# Power.net
KiCad netlist of a schematic drawn in Altium Designer
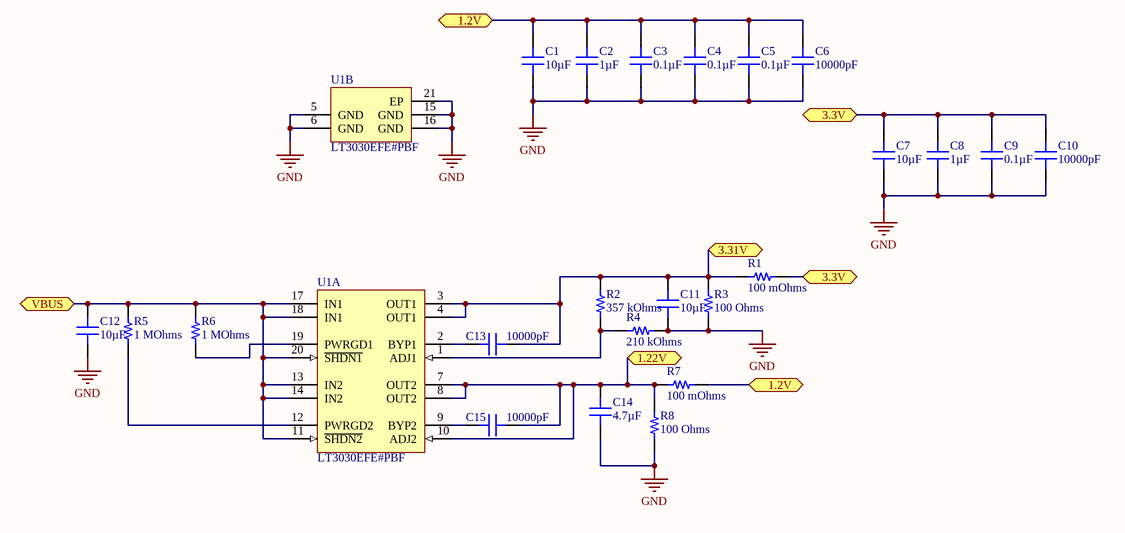
[diagram p0: Power.SchDoc]

(export (version "E")
  (design (tool "Eeschema 10.0.6"))
  (components
    (comp (ref "C1")
      (value "10µF")
      (footprint "CAP 0805_2012")
      (description "CAP CER 10UF 16V X5R 0805")
      (fields
        (field (name "PART NUMBER") "CL21A106KOQNNNG")
        (field (name "MANUFACTURER") "Samsung Electro-Mechanics")
      )
      (libsource (lib "Celestial Altium Library - altium_library") (part "Capacitor"))
    )
    (comp (ref "C2")
      (value "1µF")
      (footprint "CAP 0805_2012")
      (description "CAP CER 1UF 25V X7R 0805")
      (fields
        (field (name "PART NUMBER") "CL21B105KAFNNNE")
        (field (name "MANUFACTURER") "Samsung Electro-Mechanics")
      )
      (libsource (lib "Celestial Altium Library - altium_library") (part "Capacitor"))
    )
    (comp (ref "C3")
      (value "0.1µF")
      (footprint "CAP 0805_2012")
      (description "CAP CER 0.1UF 50V X7R 0805")
      (fields
        (field (name "PART NUMBER") "CL21B104KBCNNNC")
        (field (name "MANUFACTURER") "Samsung Electro-Mechanics")
      )
      (libsource (lib "Celestial Altium Library - altium_library") (part "Capacitor"))
    )
    (comp (ref "C4")
      (value "0.1µF")
      (footprint "CAP 0805_2012")
      (description "CAP CER 0.1UF 50V X7R 0805")
      (fields
        (field (name "PART NUMBER") "CL21B104KBCNNNC")
        (field (name "MANUFACTURER") "Samsung Electro-Mechanics")
      )
      (libsource (lib "Celestial Altium Library - altium_library") (part "Capacitor"))
    )
    (comp (ref "C5")
      (value "0.1µF")
      (footprint "CAP 0805_2012")
      (description "CAP CER 0.1UF 50V X7R 0805")
      (fields
        (field (name "PART NUMBER") "CL21B104KBCNNNC")
        (field (name "MANUFACTURER") "Samsung Electro-Mechanics")
      )
      (libsource (lib "Celestial Altium Library - altium_library") (part "Capacitor"))
    )
    (comp (ref "C6")
      (value "10000pF")
      (footprint "CAP 0805_2012")
      (description "CAP CER 10000PF 50V X7R 0805")
      (fields
        (field (name "PART NUMBER") "CL21B103KBANNNC")
        (field (name "MANUFACTURER") "Samsung Electro-Mechanics")
      )
      (libsource (lib "Celestial Altium Library - altium_library") (part "Capacitor"))
    )
    (comp (ref "C7")
      (value "10µF")
      (footprint "CAP 0805_2012")
      (description "CAP CER 10UF 16V X5R 0805")
      (fields
        (field (name "PART NUMBER") "CL21A106KOQNNNG")
        (field (name "MANUFACTURER") "Samsung Electro-Mechanics")
      )
      (libsource (lib "Celestial Altium Library - altium_library") (part "Capacitor"))
    )
    (comp (ref "C8")
      (value "1µF")
      (footprint "CAP 0805_2012")
      (description "CAP CER 1UF 25V X7R 0805")
      (fields
        (field (name "PART NUMBER") "CL21B105KAFNNNE")
        (field (name "MANUFACTURER") "Samsung Electro-Mechanics")
      )
      (libsource (lib "Celestial Altium Library - altium_library") (part "Capacitor"))
    )
    (comp (ref "C9")
      (value "0.1µF")
      (footprint "CAP 0805_2012")
      (description "CAP CER 0.1UF 50V X7R 0805")
      (fields
        (field (name "PART NUMBER") "CL21B104KBCNNNC")
        (field (name "MANUFACTURER") "Samsung Electro-Mechanics")
      )
      (libsource (lib "Celestial Altium Library - altium_library") (part "Capacitor"))
    )
    (comp (ref "C10")
      (value "10000pF")
      (footprint "CAP 0805_2012")
      (description "CAP CER 10000PF 50V X7R 0805")
      (fields
        (field (name "PART NUMBER") "CL21B103KBANNNC")
        (field (name "MANUFACTURER") "Samsung Electro-Mechanics")
      )
      (libsource (lib "Celestial Altium Library - altium_library") (part "Capacitor"))
    )
    (comp (ref "C11")
      (value "10µF")
      (footprint "CAP 0805_2012")
      (description "CAP CER 10UF 16V X5R 0805")
      (fields
        (field (name "PART NUMBER") "CL21A106KOQNNNG")
        (field (name "MANUFACTURER") "Samsung Electro-Mechanics")
      )
      (libsource (lib "Celestial Altium Library - altium_library") (part "Capacitor"))
    )
    (comp (ref "C12")
      (value "10µF")
      (footprint "CAP 0805_2012")
      (description "CAP CER 10UF 16V X5R 0805")
      (fields
        (field (name "PART NUMBER") "CL21A106KOQNNNG")
        (field (name "MANUFACTURER") "Samsung Electro-Mechanics")
      )
      (libsource (lib "Celestial Altium Library - altium_library") (part "Capacitor"))
    )
    (comp (ref "C13")
      (value "10000pF")
      (footprint "CAP 0805_2012")
      (description "CAP CER 10000PF 50V X7R 0805")
      (fields
        (field (name "PART NUMBER") "CL21B103KBANNNC")
        (field (name "MANUFACTURER") "Samsung Electro-Mechanics")
      )
      (libsource (lib "Celestial Altium Library - altium_library") (part "Capacitor"))
    )
    (comp (ref "C14")
      (value "4.7µF")
      (footprint "CAP 0805_2012")
      (description "CAP CER 4.7UF 25V X5R 0805")
      (fields
        (field (name "PART NUMBER") "CL21A475KAQNNNE")
        (field (name "MANUFACTURER") "Samsung Electro-Mechanics")
      )
      (libsource (lib "Celestial Altium Library - altium_library") (part "Capacitor"))
    )
    (comp (ref "C15")
      (value "10000pF")
      (footprint "CAP 0805_2012")
      (description "CAP CER 10000PF 50V X7R 0805")
      (fields
        (field (name "PART NUMBER") "CL21B103KBANNNC")
        (field (name "MANUFACTURER") "Samsung Electro-Mechanics")
      )
      (libsource (lib "Celestial Altium Library - altium_library") (part "Capacitor"))
    )
    (comp (ref "R1")
      (value "100 mOhms")
      (footprint "RES 0805_2012")
      (description "RES 0.1 OHM 1% 1/3W 0805")
      (fields (field (name "PART NUMBER") "RL1220S-R10-F") (field (name "MANUFACTURER") "Susumu"))
      (libsource (lib "Celestial Altium Library - altium_library") (part "Resistor"))
    )
    (comp (ref "R2")
      (value "357 kOhms")
      (footprint "RES 0805_2012")
      (description "RES SMD 357K OHM 1% 1/8W 0805")
      (fields
        (field (name "PART NUMBER") "ERJ-6ENF3573V")
        (field (name "MANUFACTURER") "Panasonic Electronic Components")
      )
      (libsource (lib "Celestial Altium Library - altium_library") (part "Resistor"))
    )
    (comp (ref "R3")
      (value "100 Ohms")
      (footprint "RES 0805_2012")
      (description "RES 100 OHM 1% 1/4W 0805")
      (fields
        (field (name "PART NUMBER") "RNCP0805FTD100R")
        (field (name "MANUFACTURER") "Stackpole Electronics Inc")
      )
      (libsource (lib "Celestial Altium Library - altium_library") (part "Resistor"))
    )
    (comp (ref "R4")
      (value "210 kOhms")
      (footprint "RES 0805_2012")
      (description "RES SMD 210K OHM 1% 1/8W 0805")
      (fields
        (field (name "PART NUMBER") "ERJ-6ENF2103V")
        (field (name "MANUFACTURER") "Panasonic Electronic Components")
      )
      (libsource (lib "Celestial Altium Library - altium_library") (part "Resistor"))
    )
    (comp (ref "R5")
      (value "1 MOhms")
      (footprint "RES 0805_2012")
      (description "RES 1M OHM 1% 1/8W 0805")
      (fields
        (field (name "PART NUMBER") "RMCF0805FG1M00")
        (field (name "MANUFACTURER") "Stackpole Electronics Inc")
      )
      (libsource (lib "Celestial Altium Library - altium_library") (part "Resistor"))
    )
    (comp (ref "R6")
      (value "1 MOhms")
      (footprint "RES 0805_2012")
      (description "RES 1M OHM 1% 1/8W 0805")
      (fields
        (field (name "PART NUMBER") "RMCF0805FG1M00")
        (field (name "MANUFACTURER") "Stackpole Electronics Inc")
      )
      (libsource (lib "Celestial Altium Library - altium_library") (part "Resistor"))
    )
    (comp (ref "R7")
      (value "100 mOhms")
      (footprint "RES 0805_2012")
      (description "RES 0.1 OHM 1% 1/3W 0805")
      (fields (field (name "PART NUMBER") "RL1220S-R10-F") (field (name "MANUFACTURER") "Susumu"))
      (libsource (lib "Celestial Altium Library - altium_library") (part "Resistor"))
    )
    (comp (ref "R8")
      (value "100 Ohms")
      (footprint "RES 0805_2012")
      (description "RES 100 OHM 1% 1/4W 0805")
      (fields
        (field (name "PART NUMBER") "RNCP0805FTD100R")
        (field (name "MANUFACTURER") "Stackpole Electronics Inc")
      )
      (libsource (lib "Celestial Altium Library - altium_library") (part "Resistor"))
    )
    (comp (ref "U1")
      (value "LT3030EFE#PBF")
      (footprint "LT-FE-20-EPV-CB_M")
      (fields (field (name "MANUFACTURER") "Linear Technology"))
      (libsource (lib "Altium Content Vault") (part "LT-LT3030-FE-20"))
    )
  )
  (nets
    (net (code "1") (name "/1.2V") (class "Default")
      (node (ref "C1") (pin "2") (pinfunction "2_2") (pintype "passive"))
      (node (ref "C2") (pin "2") (pinfunction "2_2") (pintype "passive"))
      (node (ref "C3") (pin "2") (pinfunction "2_2") (pintype "passive"))
      (node (ref "C4") (pin "2") (pinfunction "2_2") (pintype "passive"))
      (node (ref "C5") (pin "2") (pinfunction "2_2") (pintype "passive"))
      (node (ref "C6") (pin "1") (pinfunction "1_1") (pintype "passive"))
      (node (ref "R7") (pin "2") (pinfunction "2_2") (pintype "passive"))
    )
    (net (code "2") (name "/1.22V") (class "Default")
      (node (ref "C14") (pin "2") (pinfunction "2_2") (pintype "passive"))
      (node (ref "C15") (pin "1") (pinfunction "1_1") (pintype "passive"))
      (node (ref "R7") (pin "1") (pinfunction "1_1") (pintype "passive"))
      (node (ref "R8") (pin "2") (pinfunction "2_2") (pintype "passive"))
      (node (ref "U1") (pin "10") (pinfunction "ADJ2_10") (pintype "input"))
      (node (ref "U1") (pin "7") (pinfunction "OUT2_7") (pintype "power_in"))
      (node (ref "U1") (pin "8") (pinfunction "OUT2_8") (pintype "power_in"))
    )
    (net (code "3") (name "/3.3V") (class "Default")
      (node (ref "C10") (pin "1") (pinfunction "1_1") (pintype "passive"))
      (node (ref "C7") (pin "2") (pinfunction "2_2") (pintype "passive"))
      (node (ref "C8") (pin "2") (pinfunction "2_2") (pintype "passive"))
      (node (ref "C9") (pin "2") (pinfunction "2_2") (pintype "passive"))
      (node (ref "R1") (pin "2") (pinfunction "2_2") (pintype "passive"))
    )
    (net (code "4") (name "/3.31V") (class "Default")
      (node (ref "C11") (pin "2") (pinfunction "2_2") (pintype "passive"))
      (node (ref "C13") (pin "1") (pinfunction "1_1") (pintype "passive"))
      (node (ref "R1") (pin "1") (pinfunction "1_1") (pintype "passive"))
      (node (ref "R2") (pin "2") (pinfunction "2_2") (pintype "passive"))
      (node (ref "R3") (pin "2") (pinfunction "2_2") (pintype "passive"))
      (node (ref "U1") (pin "3") (pinfunction "OUT1_3") (pintype "power_in"))
      (node (ref "U1") (pin "4") (pinfunction "OUT1_4") (pintype "power_in"))
    )
    (net (code "5") (name "/VBUS") (class "Default")
      (node (ref "C12") (pin "2") (pinfunction "2_2") (pintype "passive"))
      (node (ref "R5") (pin "2") (pinfunction "2_2") (pintype "passive"))
      (node (ref "R6") (pin "2") (pinfunction "2_2") (pintype "passive"))
      (node (ref "U1") (pin "11") (pinfunction "~{SHDN2}_11") (pintype "input"))
      (node (ref "U1") (pin "13") (pinfunction "IN2_13") (pintype "power_in"))
      (node (ref "U1") (pin "14") (pinfunction "IN2_14") (pintype "power_in"))
      (node (ref "U1") (pin "17") (pinfunction "IN1_17") (pintype "power_in"))
      (node (ref "U1") (pin "18") (pinfunction "IN1_18") (pintype "power_in"))
      (node (ref "U1") (pin "20") (pinfunction "~{SHDN1}_20") (pintype "input"))
    )
    (net (code "6") (name "GND") (class "Default")
      (node (ref "C1") (pin "1") (pinfunction "1_1") (pintype "passive"))
      (node (ref "C10") (pin "2") (pinfunction "2_2") (pintype "passive"))
      (node (ref "C11") (pin "1") (pinfunction "1_1") (pintype "passive"))
      (node (ref "C12") (pin "1") (pinfunction "1_1") (pintype "passive"))
      (node (ref "C14") (pin "1") (pinfunction "1_1") (pintype "passive"))
      (node (ref "C2") (pin "1") (pinfunction "1_1") (pintype "passive"))
      (node (ref "C3") (pin "1") (pinfunction "1_1") (pintype "passive"))
      (node (ref "C4") (pin "1") (pinfunction "1_1") (pintype "passive"))
      (node (ref "C5") (pin "1") (pinfunction "1_1") (pintype "passive"))
      (node (ref "C6") (pin "2") (pinfunction "2_2") (pintype "passive"))
      (node (ref "C7") (pin "1") (pinfunction "1_1") (pintype "passive"))
      (node (ref "C8") (pin "1") (pinfunction "1_1") (pintype "passive"))
      (node (ref "C9") (pin "1") (pinfunction "1_1") (pintype "passive"))
      (node (ref "R3") (pin "1") (pinfunction "1_1") (pintype "passive"))
      (node (ref "R4") (pin "2") (pinfunction "2_2") (pintype "passive"))
      (node (ref "R8") (pin "1") (pinfunction "1_1") (pintype "passive"))
      (node (ref "U1") (pin "15") (pinfunction "GND_15") (pintype "power_in"))
      (node (ref "U1") (pin "16") (pinfunction "GND_16") (pintype "power_in"))
      (node (ref "U1") (pin "21") (pinfunction "EP_21") (pintype "power_in"))
      (node (ref "U1") (pin "5") (pinfunction "GND_5") (pintype "power_in"))
      (node (ref "U1") (pin "6") (pinfunction "GND_6") (pintype "power_in"))
    )
    (net (code "7") (name "Net-(U1A-ADJ1)") (class "Default")
      (node (ref "R2") (pin "1") (pinfunction "1_1") (pintype "passive"))
      (node (ref "R4") (pin "1") (pinfunction "1_1") (pintype "passive"))
      (node (ref "U1") (pin "1") (pinfunction "ADJ1_1") (pintype "input"))
    )
    (net (code "8") (name "Net-(U1A-BYP1)") (class "Default")
      (node (ref "C13") (pin "2") (pinfunction "2_2") (pintype "passive"))
      (node (ref "U1") (pin "2") (pinfunction "BYP1_2") (pintype "passive"))
    )
    (net (code "9") (name "Net-(U1A-BYP2)") (class "Default")
      (node (ref "C15") (pin "2") (pinfunction "2_2") (pintype "passive"))
      (node (ref "U1") (pin "9") (pinfunction "BYP2_9") (pintype "passive"))
    )
    (net (code "10") (name "Net-(U1A-PWRGD1)") (class "Default")
      (node (ref "R6") (pin "1") (pinfunction "1_1") (pintype "passive"))
      (node (ref "U1") (pin "19") (pinfunction "PWRGD1_19") (pintype "tri_state"))
    )
    (net (code "11") (name "Net-(U1A-PWRGD2)") (class "Default")
      (node (ref "R5") (pin "1") (pinfunction "1_1") (pintype "passive"))
      (node (ref "U1") (pin "12") (pinfunction "PWRGD2_12") (pintype "tri_state"))
    )
  )
)
